# TeslaBMS_Shield_4.net
KiCad netlist of a schematic drawn in EAGLE
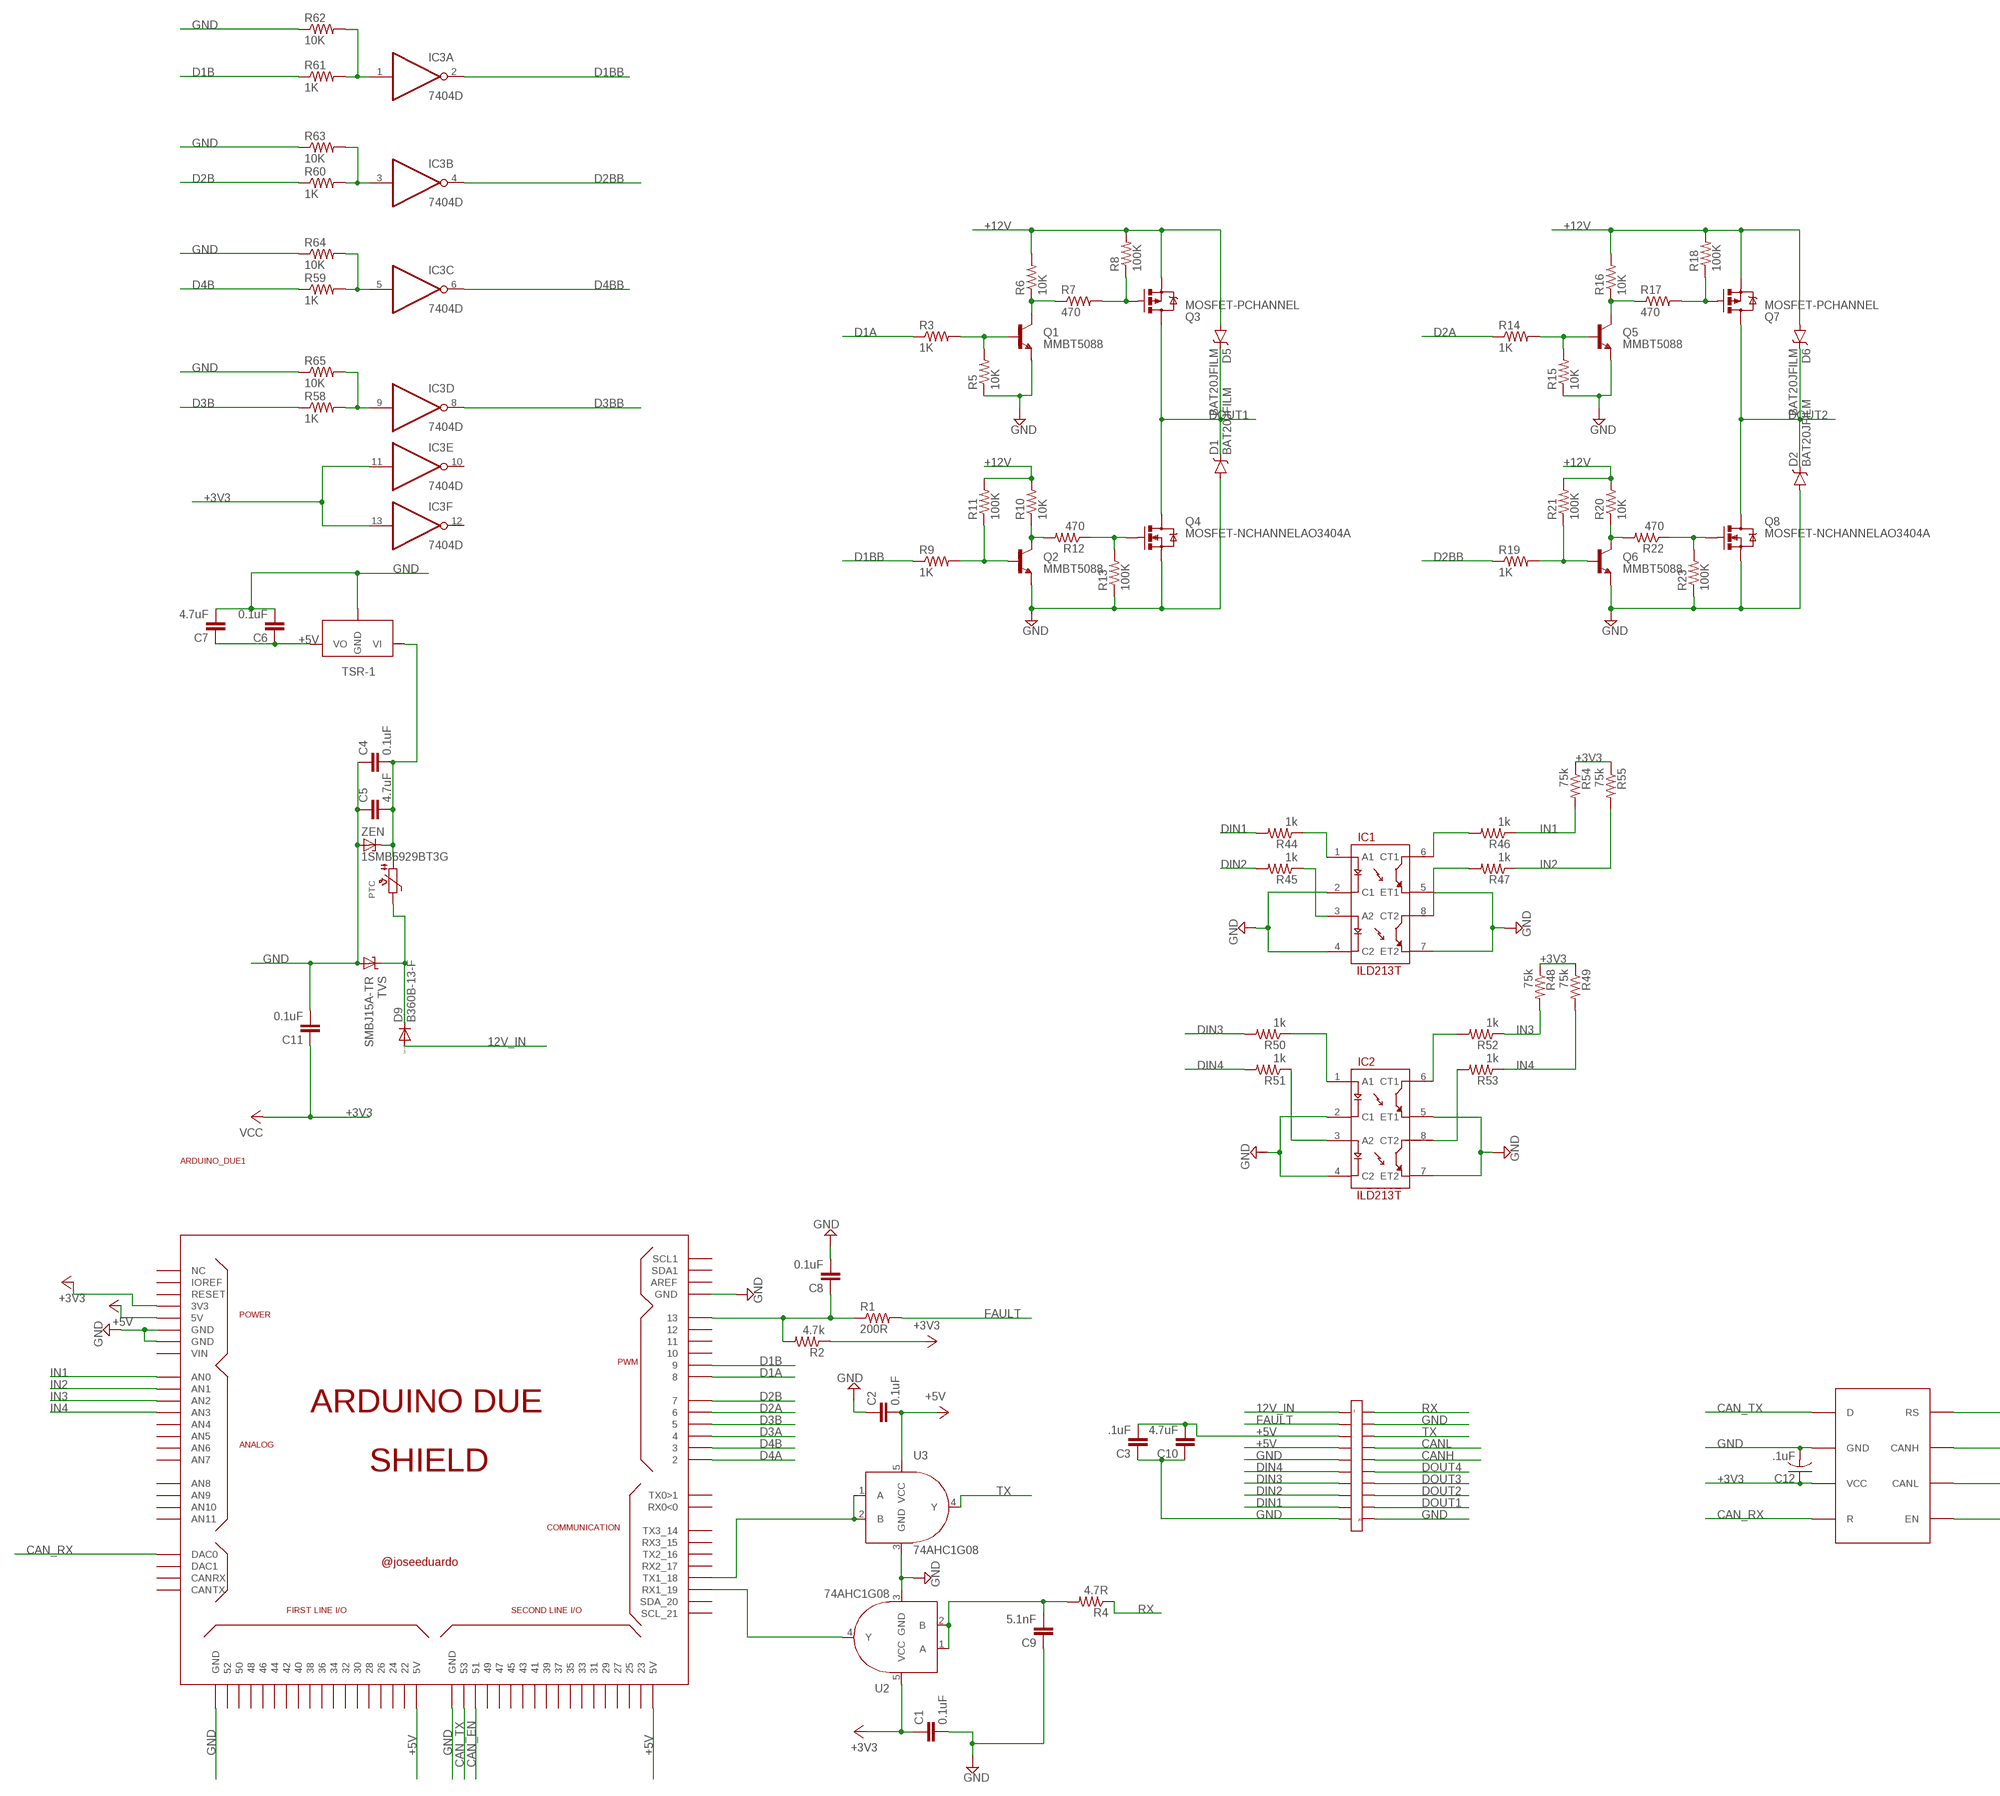
[diagram p0: schematic, sheet 1, part 1 of 2]
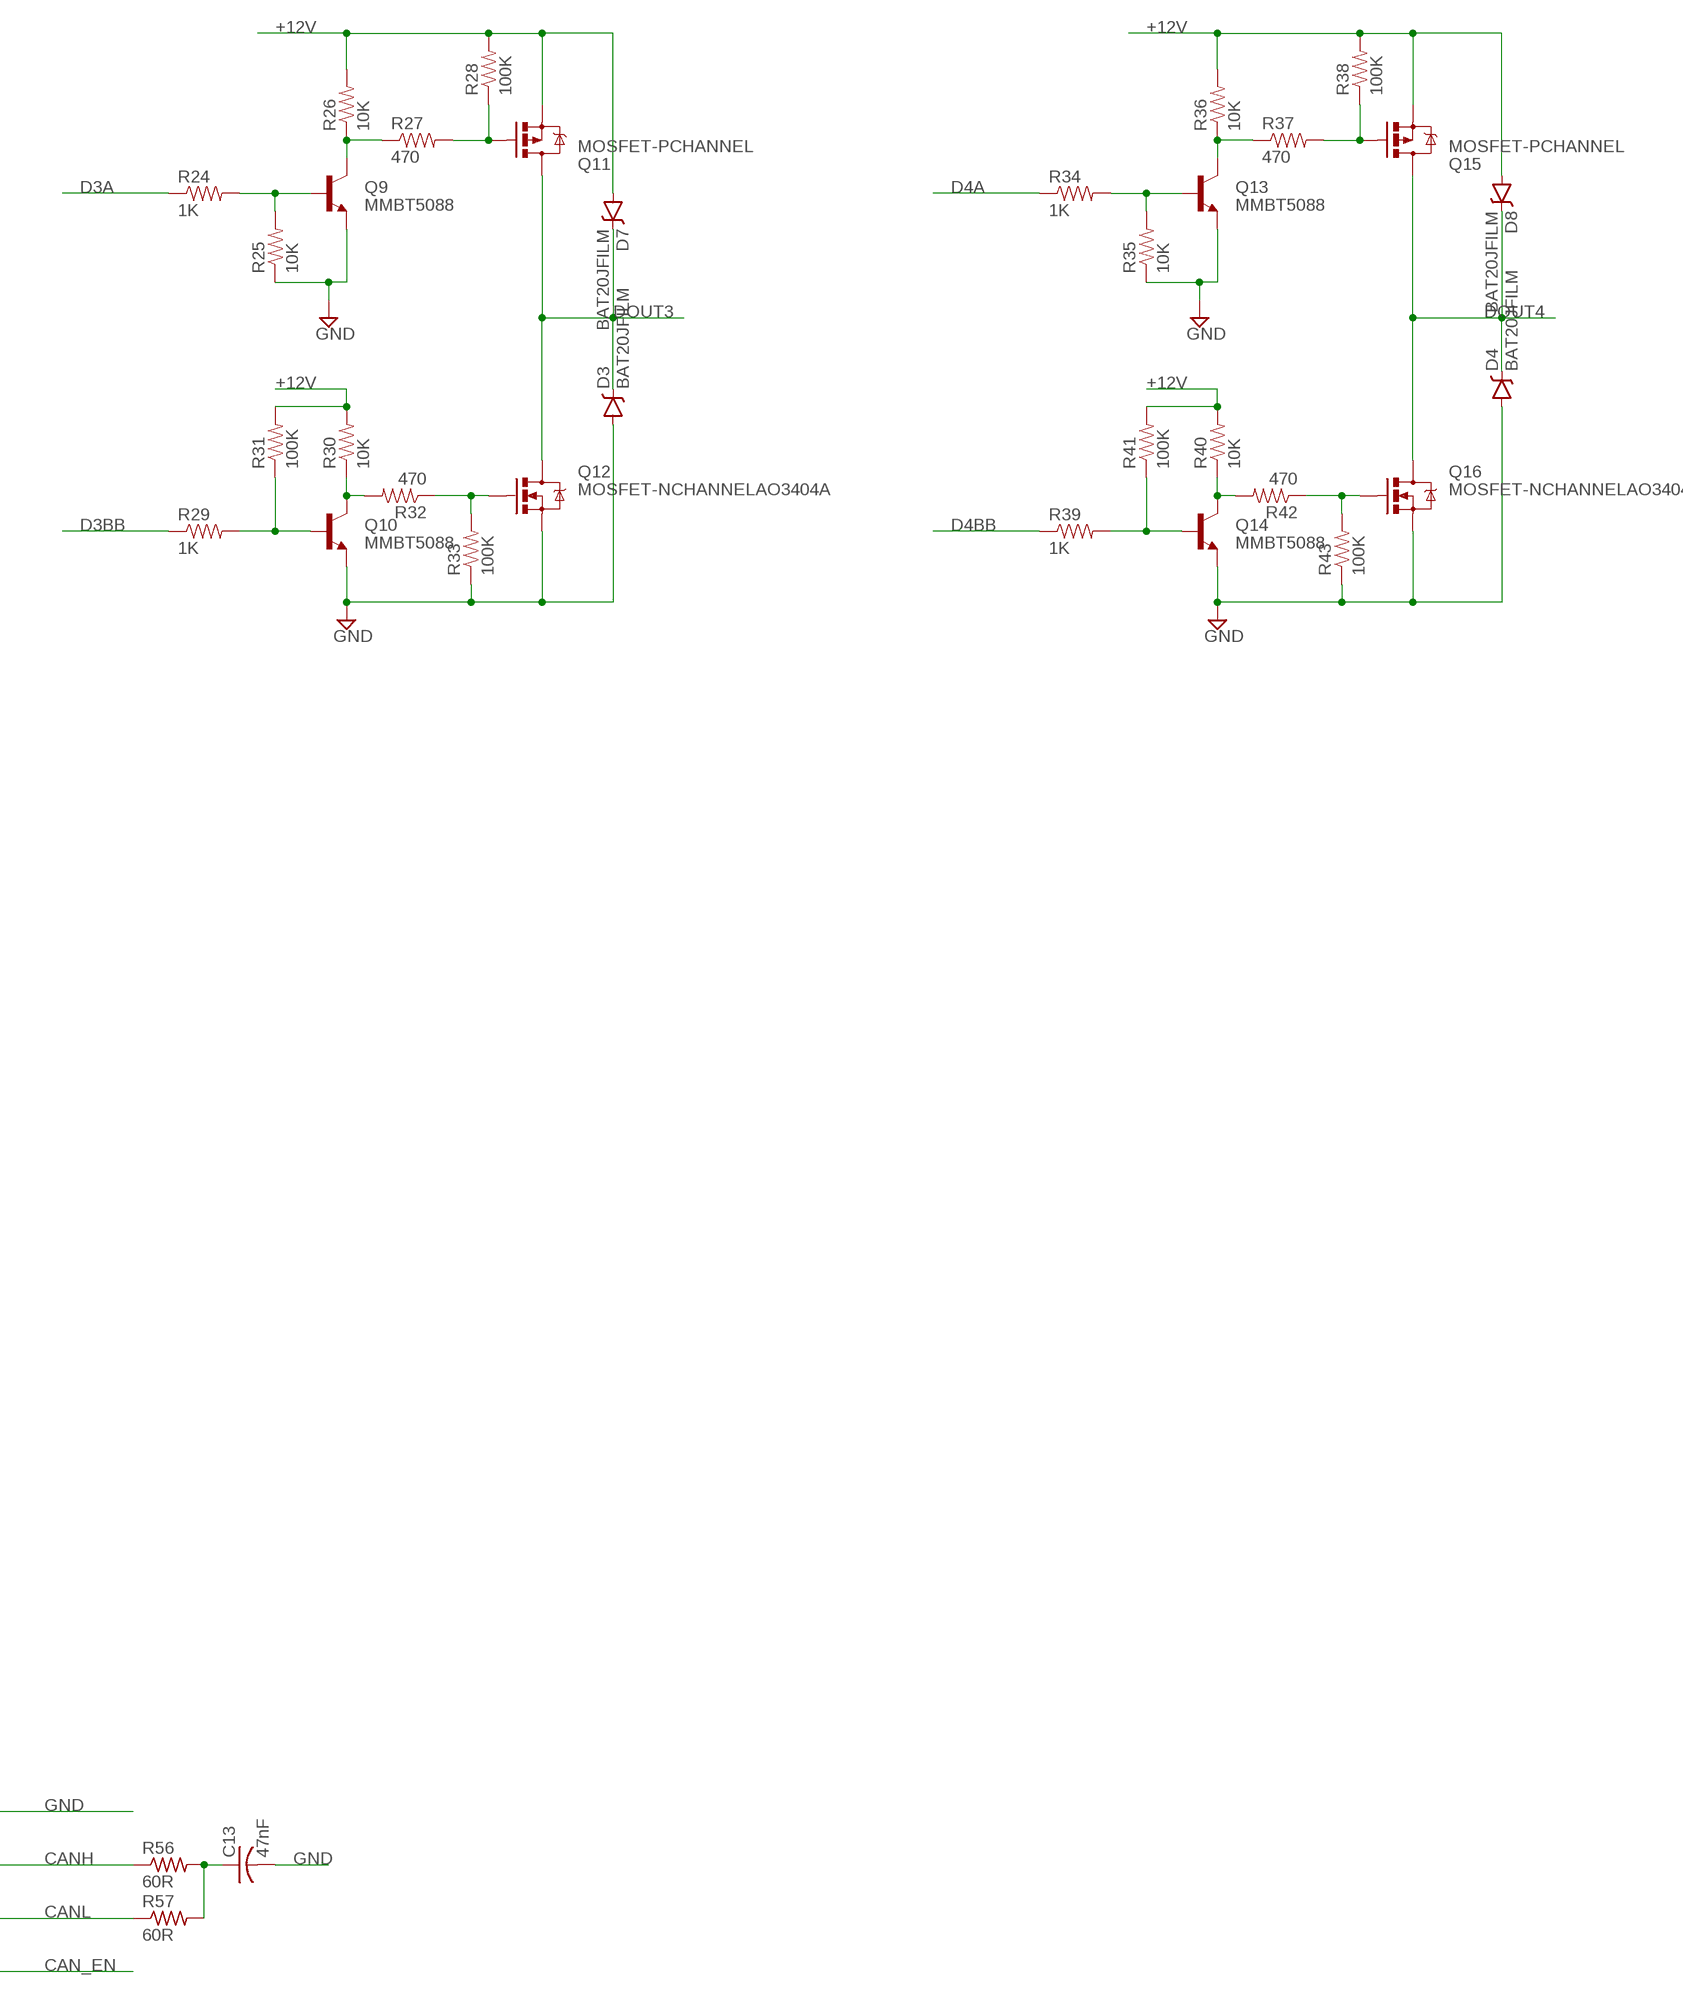
[diagram p1: schematic, sheet 1, part 2 of 2]

(export (version "E")
  (design (tool "Eeschema 10.0.6"))
  (components
    (comp (ref "ARDUINO_DUE1")
      (value "ARDUINO_DUE_SHIELD")
      (footprint "eagle-import:ARDUINO_DUE_SHIELD")
      (libsource (lib "eagle-import") (part "ARDUINO_DUE_SHIELD"))
    )
    (comp (ref "C1")
      (value "0.1uF")
      (footprint "eagle-import:0603-CAP")
      (libsource (lib "eagle-import") (part "CAP0603-CAP"))
    )
    (comp (ref "C2")
      (value "0.1uF")
      (footprint "eagle-import:0603-CAP")
      (libsource (lib "eagle-import") (part "CAP0603-CAP"))
    )
    (comp (ref "C3")
      (value ".1uF")
      (footprint "eagle-import:0603-CAP")
      (libsource (lib "eagle-import") (part "CAP0603-CAP"))
    )
    (comp (ref "C4")
      (value "0.1uF")
      (footprint "eagle-import:0805")
      (libsource (lib "eagle-import") (part "CAP0805"))
    )
    (comp (ref "C5")
      (value "4.7uF")
      (footprint "eagle-import:0805")
      (libsource (lib "eagle-import") (part "CAP0805"))
    )
    (comp (ref "C6")
      (value "0.1uF")
      (footprint "eagle-import:0805")
      (libsource (lib "eagle-import") (part "CAP0805"))
    )
    (comp (ref "C7")
      (value "4.7uF")
      (footprint "eagle-import:0805")
      (libsource (lib "eagle-import") (part "CAP0805"))
    )
    (comp (ref "C8")
      (value "0.1uF")
      (footprint "eagle-import:0603-CAP")
      (libsource (lib "eagle-import") (part "CAP0603-CAP"))
    )
    (comp (ref "C9")
      (value "5.1nF")
      (footprint "eagle-import:0603-CAP")
      (libsource (lib "eagle-import") (part "CAP0603-CAP"))
    )
    (comp (ref "C10")
      (value "4.7uF")
      (footprint "eagle-import:0603-CAP")
      (libsource (lib "eagle-import") (part "CAP0603-CAP"))
    )
    (comp (ref "C11")
      (value "0.1uF")
      (footprint "eagle-import:0805")
      (libsource (lib "eagle-import") (part "CAP0805"))
    )
    (comp (ref "C12")
      (value ".1uF")
      (footprint "eagle-import:C0603")
      (libsource (lib "eagle-import") (part "C-USC0603"))
    )
    (comp (ref "C13")
      (value "47nF")
      (footprint "eagle-import:C0805")
      (libsource (lib "eagle-import") (part "C-USC0805"))
    )
    (comp (ref "D1")
      (value "BAT20JFILM")
      (footprint "eagle-import:SOD-323")
      (libsource (lib "eagle-import") (part "BAT20JFILM"))
    )
    (comp (ref "D2")
      (value "BAT20JFILM")
      (footprint "eagle-import:SOD-323")
      (libsource (lib "eagle-import") (part "BAT20JFILM"))
    )
    (comp (ref "D3")
      (value "BAT20JFILM")
      (footprint "eagle-import:SOD-323")
      (libsource (lib "eagle-import") (part "BAT20JFILM"))
    )
    (comp (ref "D4")
      (value "BAT20JFILM")
      (footprint "eagle-import:SOD-323")
      (libsource (lib "eagle-import") (part "BAT20JFILM"))
    )
    (comp (ref "D5")
      (value "BAT20JFILM")
      (footprint "eagle-import:SOD-323")
      (libsource (lib "eagle-import") (part "BAT20JFILM"))
    )
    (comp (ref "D6")
      (value "BAT20JFILM")
      (footprint "eagle-import:SOD-323")
      (libsource (lib "eagle-import") (part "BAT20JFILM"))
    )
    (comp (ref "D7")
      (value "BAT20JFILM")
      (footprint "eagle-import:SOD-323")
      (libsource (lib "eagle-import") (part "BAT20JFILM"))
    )
    (comp (ref "D8")
      (value "BAT20JFILM")
      (footprint "eagle-import:SOD-323")
      (libsource (lib "eagle-import") (part "BAT20JFILM"))
    )
    (comp (ref "D9")
      (value "B360B-13-F")
      (footprint "eagle-import:SMB")
      (libsource (lib "eagle-import") (part "DIODE-SMB"))
    )
    (comp (ref "IC1")
      (value "ILD213T")
      (footprint "eagle-import:SO08")
      (libsource (lib "eagle-import") (part "ILD213T"))
    )
    (comp (ref "IC2")
      (value "ILD213T")
      (footprint "eagle-import:SO08")
      (libsource (lib "eagle-import") (part "ILD213T"))
    )
    (comp (ref "IC3")
      (value "7404D")
      (footprint "eagle-import:SO14")
      (libsource (lib "eagle-import") (part "7404D"))
    )
    (comp (ref "PTC")
      (value "PTC1812")
      (footprint "eagle-import:PTC1812")
      (libsource (lib "eagle-import") (part "PTC1812"))
    )
    (comp (ref "Q1")
      (value "MMBT5088")
      (footprint "eagle-import:SOT23-3")
      (libsource (lib "eagle-import") (part "TRANSISTOR_NPNMMBT5088"))
    )
    (comp (ref "Q2")
      (value "MMBT5088")
      (footprint "eagle-import:SOT23-3")
      (libsource (lib "eagle-import") (part "TRANSISTOR_NPNMMBT5088"))
    )
    (comp (ref "Q3")
      (value "MOSFET-PCHANNEL")
      (footprint "eagle-import:SOT23-3")
      (libsource (lib "eagle-import") (part "MOSFET-PCHANNEL"))
    )
    (comp (ref "Q4")
      (value "MOSFET-NCHANNELAO3404A")
      (footprint "eagle-import:SOT23-3")
      (libsource (lib "eagle-import") (part "MOSFET-NCHANNELAO3404A"))
    )
    (comp (ref "Q5")
      (value "MMBT5088")
      (footprint "eagle-import:SOT23-3")
      (libsource (lib "eagle-import") (part "TRANSISTOR_NPNMMBT5088"))
    )
    (comp (ref "Q6")
      (value "MMBT5088")
      (footprint "eagle-import:SOT23-3")
      (libsource (lib "eagle-import") (part "TRANSISTOR_NPNMMBT5088"))
    )
    (comp (ref "Q7")
      (value "MOSFET-PCHANNEL")
      (footprint "eagle-import:SOT23-3")
      (libsource (lib "eagle-import") (part "MOSFET-PCHANNEL"))
    )
    (comp (ref "Q8")
      (value "MOSFET-NCHANNELAO3404A")
      (footprint "eagle-import:SOT23-3")
      (libsource (lib "eagle-import") (part "MOSFET-NCHANNELAO3404A"))
    )
    (comp (ref "Q9")
      (value "MMBT5088")
      (footprint "eagle-import:SOT23-3")
      (libsource (lib "eagle-import") (part "TRANSISTOR_NPNMMBT5088"))
    )
    (comp (ref "Q10")
      (value "MMBT5088")
      (footprint "eagle-import:SOT23-3")
      (libsource (lib "eagle-import") (part "TRANSISTOR_NPNMMBT5088"))
    )
    (comp (ref "Q11")
      (value "MOSFET-PCHANNEL")
      (footprint "eagle-import:SOT23-3")
      (libsource (lib "eagle-import") (part "MOSFET-PCHANNEL"))
    )
    (comp (ref "Q12")
      (value "MOSFET-NCHANNELAO3404A")
      (footprint "eagle-import:SOT23-3")
      (libsource (lib "eagle-import") (part "MOSFET-NCHANNELAO3404A"))
    )
    (comp (ref "Q13")
      (value "MMBT5088")
      (footprint "eagle-import:SOT23-3")
      (libsource (lib "eagle-import") (part "TRANSISTOR_NPNMMBT5088"))
    )
    (comp (ref "Q14")
      (value "MMBT5088")
      (footprint "eagle-import:SOT23-3")
      (libsource (lib "eagle-import") (part "TRANSISTOR_NPNMMBT5088"))
    )
    (comp (ref "Q15")
      (value "MOSFET-PCHANNEL")
      (footprint "eagle-import:SOT23-3")
      (libsource (lib "eagle-import") (part "MOSFET-PCHANNEL"))
    )
    (comp (ref "Q16")
      (value "MOSFET-NCHANNELAO3404A")
      (footprint "eagle-import:SOT23-3")
      (libsource (lib "eagle-import") (part "MOSFET-NCHANNELAO3404A"))
    )
    (comp (ref "R1")
      (value "200R")
      (footprint "eagle-import:0603-RES")
      (libsource (lib "eagle-import") (part "RESISTOR0603-RES"))
    )
    (comp (ref "R2")
      (value "4.7k")
      (footprint "eagle-import:0603-RES")
      (libsource (lib "eagle-import") (part "RESISTOR0603-RES"))
    )
    (comp (ref "R3")
      (value "1K")
      (footprint "eagle-import:0402-RES")
      (libsource (lib "eagle-import") (part "RESISTOR0402"))
    )
    (comp (ref "R4")
      (value "4.7R")
      (footprint "eagle-import:0603-RES")
      (libsource (lib "eagle-import") (part "RESISTOR0603-RES"))
    )
    (comp (ref "R5")
      (value "10K")
      (footprint "eagle-import:0402-RES")
      (libsource (lib "eagle-import") (part "RESISTOR0402"))
    )
    (comp (ref "R6")
      (value "10K")
      (footprint "eagle-import:0402-RES")
      (libsource (lib "eagle-import") (part "RESISTOR0402"))
    )
    (comp (ref "R7")
      (value "470")
      (footprint "eagle-import:0402-RES")
      (libsource (lib "eagle-import") (part "RESISTOR0402"))
    )
    (comp (ref "R8")
      (value "100K")
      (footprint "eagle-import:0402-RES")
      (libsource (lib "eagle-import") (part "RESISTOR0402"))
    )
    (comp (ref "R9")
      (value "1K")
      (footprint "eagle-import:0402-RES")
      (libsource (lib "eagle-import") (part "RESISTOR0402"))
    )
    (comp (ref "R10")
      (value "10K")
      (footprint "eagle-import:0402-RES")
      (libsource (lib "eagle-import") (part "RESISTOR0402"))
    )
    (comp (ref "R11")
      (value "100K")
      (footprint "eagle-import:0402-RES")
      (libsource (lib "eagle-import") (part "RESISTOR0402"))
    )
    (comp (ref "R12")
      (value "470")
      (footprint "eagle-import:0402-RES")
      (libsource (lib "eagle-import") (part "RESISTOR0402"))
    )
    (comp (ref "R13")
      (value "100K")
      (footprint "eagle-import:0402-RES")
      (libsource (lib "eagle-import") (part "RESISTOR0402"))
    )
    (comp (ref "R14")
      (value "1K")
      (footprint "eagle-import:0402-RES")
      (libsource (lib "eagle-import") (part "RESISTOR0402"))
    )
    (comp (ref "R15")
      (value "10K")
      (footprint "eagle-import:0402-RES")
      (libsource (lib "eagle-import") (part "RESISTOR0402"))
    )
    (comp (ref "R16")
      (value "10K")
      (footprint "eagle-import:0402-RES")
      (libsource (lib "eagle-import") (part "RESISTOR0402"))
    )
    (comp (ref "R17")
      (value "470")
      (footprint "eagle-import:0402-RES")
      (libsource (lib "eagle-import") (part "RESISTOR0402"))
    )
    (comp (ref "R18")
      (value "100K")
      (footprint "eagle-import:0402-RES")
      (libsource (lib "eagle-import") (part "RESISTOR0402"))
    )
    (comp (ref "R19")
      (value "1K")
      (footprint "eagle-import:0402-RES")
      (libsource (lib "eagle-import") (part "RESISTOR0402"))
    )
    (comp (ref "R20")
      (value "10K")
      (footprint "eagle-import:0402-RES")
      (libsource (lib "eagle-import") (part "RESISTOR0402"))
    )
    (comp (ref "R21")
      (value "100K")
      (footprint "eagle-import:0402-RES")
      (libsource (lib "eagle-import") (part "RESISTOR0402"))
    )
    (comp (ref "R22")
      (value "470")
      (footprint "eagle-import:0402-RES")
      (libsource (lib "eagle-import") (part "RESISTOR0402"))
    )
    (comp (ref "R23")
      (value "100K")
      (footprint "eagle-import:0402-RES")
      (libsource (lib "eagle-import") (part "RESISTOR0402"))
    )
    (comp (ref "R24")
      (value "1K")
      (footprint "eagle-import:0402-RES")
      (libsource (lib "eagle-import") (part "RESISTOR0402"))
    )
    (comp (ref "R25")
      (value "10K")
      (footprint "eagle-import:0402-RES")
      (libsource (lib "eagle-import") (part "RESISTOR0402"))
    )
    (comp (ref "R26")
      (value "10K")
      (footprint "eagle-import:0402-RES")
      (libsource (lib "eagle-import") (part "RESISTOR0402"))
    )
    (comp (ref "R27")
      (value "470")
      (footprint "eagle-import:0402-RES")
      (libsource (lib "eagle-import") (part "RESISTOR0402"))
    )
    (comp (ref "R28")
      (value "100K")
      (footprint "eagle-import:0402-RES")
      (libsource (lib "eagle-import") (part "RESISTOR0402"))
    )
    (comp (ref "R29")
      (value "1K")
      (footprint "eagle-import:0402-RES")
      (libsource (lib "eagle-import") (part "RESISTOR0402"))
    )
    (comp (ref "R30")
      (value "10K")
      (footprint "eagle-import:0402-RES")
      (libsource (lib "eagle-import") (part "RESISTOR0402"))
    )
    (comp (ref "R31")
      (value "100K")
      (footprint "eagle-import:0402-RES")
      (libsource (lib "eagle-import") (part "RESISTOR0402"))
    )
    (comp (ref "R32")
      (value "470")
      (footprint "eagle-import:0402-RES")
      (libsource (lib "eagle-import") (part "RESISTOR0402"))
    )
    (comp (ref "R33")
      (value "100K")
      (footprint "eagle-import:0402-RES")
      (libsource (lib "eagle-import") (part "RESISTOR0402"))
    )
    (comp (ref "R34")
      (value "1K")
      (footprint "eagle-import:0402-RES")
      (libsource (lib "eagle-import") (part "RESISTOR0402"))
    )
    (comp (ref "R35")
      (value "10K")
      (footprint "eagle-import:0402-RES")
      (libsource (lib "eagle-import") (part "RESISTOR0402"))
    )
    (comp (ref "R36")
      (value "10K")
      (footprint "eagle-import:0402-RES")
      (libsource (lib "eagle-import") (part "RESISTOR0402"))
    )
    (comp (ref "R37")
      (value "470")
      (footprint "eagle-import:0402-RES")
      (libsource (lib "eagle-import") (part "RESISTOR0402"))
    )
    (comp (ref "R38")
      (value "100K")
      (footprint "eagle-import:0402-RES")
      (libsource (lib "eagle-import") (part "RESISTOR0402"))
    )
    (comp (ref "R39")
      (value "1K")
      (footprint "eagle-import:0402-RES")
      (libsource (lib "eagle-import") (part "RESISTOR0402"))
    )
    (comp (ref "R40")
      (value "10K")
      (footprint "eagle-import:0402-RES")
      (libsource (lib "eagle-import") (part "RESISTOR0402"))
    )
    (comp (ref "R41")
      (value "100K")
      (footprint "eagle-import:0402-RES")
      (libsource (lib "eagle-import") (part "RESISTOR0402"))
    )
    (comp (ref "R42")
      (value "470")
      (footprint "eagle-import:0402-RES")
      (libsource (lib "eagle-import") (part "RESISTOR0402"))
    )
    (comp (ref "R43")
      (value "100K")
      (footprint "eagle-import:0402-RES")
      (libsource (lib "eagle-import") (part "RESISTOR0402"))
    )
    (comp (ref "R44")
      (value "1k")
      (footprint "eagle-import:0603-RES")
      (libsource (lib "eagle-import") (part "RESISTOR0603-RES"))
    )
    (comp (ref "R45")
      (value "1k")
      (footprint "eagle-import:0603-RES")
      (libsource (lib "eagle-import") (part "RESISTOR0603-RES"))
    )
    (comp (ref "R46")
      (value "1k")
      (footprint "eagle-import:0603-RES")
      (libsource (lib "eagle-import") (part "RESISTOR0603-RES"))
    )
    (comp (ref "R47")
      (value "1k")
      (footprint "eagle-import:0603-RES")
      (libsource (lib "eagle-import") (part "RESISTOR0603-RES"))
    )
    (comp (ref "R48")
      (value "75k")
      (footprint "eagle-import:0603-RES")
      (libsource (lib "eagle-import") (part "RESISTOR0603-RES"))
    )
    (comp (ref "R49")
      (value "75k")
      (footprint "eagle-import:0603-RES")
      (libsource (lib "eagle-import") (part "RESISTOR0603-RES"))
    )
    (comp (ref "R50")
      (value "1k")
      (footprint "eagle-import:0603-RES")
      (libsource (lib "eagle-import") (part "RESISTOR0603-RES"))
    )
    (comp (ref "R51")
      (value "1k")
      (footprint "eagle-import:0603-RES")
      (libsource (lib "eagle-import") (part "RESISTOR0603-RES"))
    )
    (comp (ref "R52")
      (value "1k")
      (footprint "eagle-import:0603-RES")
      (libsource (lib "eagle-import") (part "RESISTOR0603-RES"))
    )
    (comp (ref "R53")
      (value "1k")
      (footprint "eagle-import:0603-RES")
      (libsource (lib "eagle-import") (part "RESISTOR0603-RES"))
    )
    (comp (ref "R54")
      (value "75k")
      (footprint "eagle-import:0603-RES")
      (libsource (lib "eagle-import") (part "RESISTOR0603-RES"))
    )
    (comp (ref "R55")
      (value "75k")
      (footprint "eagle-import:0603-RES")
      (libsource (lib "eagle-import") (part "RESISTOR0603-RES"))
    )
    (comp (ref "R56")
      (value "60R")
      (footprint "eagle-import:M0805")
      (libsource (lib "eagle-import") (part "R-US_M0805"))
    )
    (comp (ref "R57")
      (value "60R")
      (footprint "eagle-import:M0805")
      (libsource (lib "eagle-import") (part "R-US_M0805"))
    )
    (comp (ref "R58")
      (value "1K")
      (footprint "eagle-import:0402-RES")
      (libsource (lib "eagle-import") (part "RESISTOR0402"))
    )
    (comp (ref "R59")
      (value "1K")
      (footprint "eagle-import:0402-RES")
      (libsource (lib "eagle-import") (part "RESISTOR0402"))
    )
    (comp (ref "R60")
      (value "1K")
      (footprint "eagle-import:0402-RES")
      (libsource (lib "eagle-import") (part "RESISTOR0402"))
    )
    (comp (ref "R61")
      (value "1K")
      (footprint "eagle-import:0402-RES")
      (libsource (lib "eagle-import") (part "RESISTOR0402"))
    )
    (comp (ref "R62")
      (value "10K")
      (footprint "eagle-import:0402-RES")
      (libsource (lib "eagle-import") (part "RESISTOR0402"))
    )
    (comp (ref "R63")
      (value "10K")
      (footprint "eagle-import:0402-RES")
      (libsource (lib "eagle-import") (part "RESISTOR0402"))
    )
    (comp (ref "R64")
      (value "10K")
      (footprint "eagle-import:0402-RES")
      (libsource (lib "eagle-import") (part "RESISTOR0402"))
    )
    (comp (ref "R65")
      (value "10K")
      (footprint "eagle-import:0402-RES")
      (libsource (lib "eagle-import") (part "RESISTOR0402"))
    )
    (comp (ref "TVS")
      (value "SMBJ15A-TR")
      (footprint "eagle-import:SMBJ")
      (libsource (lib "eagle-import") (part "SUPPRESSOR-SMBJ"))
    )
    (comp (ref "U$2")
      (value "VAL-U-LOK-20PIN")
      (footprint "eagle-import:VALULOK-20")
      (libsource (lib "eagle-import") (part "VAL-U-LOK-20PIN"))
    )
    (comp (ref "U1")
      (value "SN65HVD234")
      (footprint "eagle-import:SOIC8")
      (libsource (lib "eagle-import") (part "SN65HVD234"))
    )
    (comp (ref "U2")
      (value "74AHC1G08")
      (footprint "eagle-import:SOT353")
      (libsource (lib "eagle-import") (part "74AHC1G08"))
    )
    (comp (ref "U3")
      (value "74AHC1G08")
      (footprint "eagle-import:SOT353")
      (libsource (lib "eagle-import") (part "74AHC1G08"))
    )
    (comp (ref "U9")
      (value "TSR-1")
      (footprint "eagle-import:TSR-1")
      (libsource (lib "eagle-import") (part "TSR-1"))
    )
    (comp (ref "ZEN")
      (value "1SMB5929BT3G")
      (footprint "eagle-import:SMB")
      (libsource (lib "eagle-import") (part "ZENER-DIODESMB"))
    )
  )
  (nets
    (net (code "1") (name "+3V3") (class "Default")
      (node (ref "ARDUINO_DUE1") (pin "3V3") (pinfunction "3V3_3V3") (pintype "bidirectional"))
      (node (ref "C1") (pin "1") (pinfunction "1_1") (pintype "passive"))
      (node (ref "C11") (pin "1") (pinfunction "1_1") (pintype "passive"))
      (node (ref "C12") (pin "1") (pinfunction "1_1") (pintype "passive"))
      (node (ref "IC3") (pin "11") (pinfunction "I_11") (pintype "input"))
      (node (ref "IC3") (pin "13") (pinfunction "I_13") (pintype "input"))
      (node (ref "R2") (pin "1") (pinfunction "1_1") (pintype "passive"))
      (node (ref "R48") (pin "1") (pinfunction "1_1") (pintype "passive"))
      (node (ref "R49") (pin "1") (pinfunction "1_1") (pintype "passive"))
      (node (ref "R54") (pin "1") (pinfunction "1_1") (pintype "passive"))
      (node (ref "R55") (pin "1") (pinfunction "1_1") (pintype "passive"))
      (node (ref "U1") (pin "PIN3") (pinfunction "VCC_PIN3") (pintype "bidirectional"))
      (node (ref "U2") (pin "5") (pinfunction "VCC_5") (pintype "bidirectional"))
    )
    (net (code "2") (name "+5V") (class "Default")
      (node (ref "ARDUINO_DUE1") (pin "5V0") (pinfunction "5V_5V0") (pintype "bidirectional"))
      (node (ref "ARDUINO_DUE1") (pin "5V0_1") (pinfunction "5V_5V0_1") (pintype "bidirectional"))
      (node (ref "ARDUINO_DUE1") (pin "5V0_2") (pinfunction "5V_5V0_2") (pintype "bidirectional"))
      (node (ref "C10") (pin "2") (pinfunction "2_2") (pintype "passive"))
      (node (ref "C2") (pin "2") (pinfunction "2_2") (pintype "passive"))
      (node (ref "C3") (pin "2") (pinfunction "2_2") (pintype "passive"))
      (node (ref "C6") (pin "1") (pinfunction "1_1") (pintype "passive"))
      (node (ref "C7") (pin "1") (pinfunction "1_1") (pintype "passive"))
      (node (ref "U$2") (pin "P$3") (pinfunction "P$3_P$3") (pintype "bidirectional"))
      (node (ref "U$2") (pin "P$4") (pinfunction "P$4_P$4") (pintype "bidirectional"))
      (node (ref "U3") (pin "5") (pinfunction "VCC_5") (pintype "bidirectional"))
      (node (ref "U9") (pin "P$3") (pinfunction "VO_P$3") (pintype "bidirectional"))
    )
    (net (code "3") (name "/+12V") (class "Default")
      (node (ref "C4") (pin "2") (pinfunction "2_2") (pintype "passive"))
      (node (ref "C5") (pin "2") (pinfunction "2_2") (pintype "passive"))
      (node (ref "D5") (pin "A") (pinfunction "A_A") (pintype "passive"))
      (node (ref "D6") (pin "A") (pinfunction "A_A") (pintype "passive"))
      (node (ref "D7") (pin "A") (pinfunction "A_A") (pintype "passive"))
      (node (ref "D8") (pin "A") (pinfunction "A_A") (pintype "passive"))
      (node (ref "PTC") (pin "P$1") (pinfunction "1_P$1") (pintype "passive"))
      (node (ref "Q11") (pin "2") (pinfunction "S_2") (pintype "passive"))
      (node (ref "Q15") (pin "2") (pinfunction "S_2") (pintype "passive"))
      (node (ref "Q3") (pin "2") (pinfunction "S_2") (pintype "passive"))
      (node (ref "Q7") (pin "2") (pinfunction "S_2") (pintype "passive"))
      (node (ref "R10") (pin "2") (pinfunction "2_2") (pintype "passive"))
      (node (ref "R11") (pin "2") (pinfunction "2_2") (pintype "passive"))
      (node (ref "R16") (pin "2") (pinfunction "2_2") (pintype "passive"))
      (node (ref "R18") (pin "2") (pinfunction "2_2") (pintype "passive"))
      (node (ref "R20") (pin "2") (pinfunction "2_2") (pintype "passive"))
      (node (ref "R21") (pin "2") (pinfunction "2_2") (pintype "passive"))
      (node (ref "R26") (pin "2") (pinfunction "2_2") (pintype "passive"))
      (node (ref "R28") (pin "2") (pinfunction "2_2") (pintype "passive"))
      (node (ref "R30") (pin "2") (pinfunction "2_2") (pintype "passive"))
      (node (ref "R31") (pin "2") (pinfunction "2_2") (pintype "passive"))
      (node (ref "R36") (pin "2") (pinfunction "2_2") (pintype "passive"))
      (node (ref "R38") (pin "2") (pinfunction "2_2") (pintype "passive"))
      (node (ref "R40") (pin "2") (pinfunction "2_2") (pintype "passive"))
      (node (ref "R41") (pin "2") (pinfunction "2_2") (pintype "passive"))
      (node (ref "R6") (pin "2") (pinfunction "2_2") (pintype "passive"))
      (node (ref "R8") (pin "2") (pinfunction "2_2") (pintype "passive"))
      (node (ref "U9") (pin "P$1") (pinfunction "VI_P$1") (pintype "bidirectional"))
      (node (ref "ZEN") (pin "C") (pinfunction "C_C") (pintype "passive"))
    )
    (net (code "4") (name "/12V_IN") (class "Default")
      (node (ref "D9") (pin "A") (pinfunction "A_A") (pintype "passive"))
      (node (ref "U$2") (pin "P$1") (pinfunction "P$1_P$1") (pintype "bidirectional"))
    )
    (net (code "5") (name "/CANH") (class "Default")
      (node (ref "R56") (pin "1") (pinfunction "1_1") (pintype "passive"))
      (node (ref "U$2") (pin "P$15") (pinfunction "P$15_P$15") (pintype "bidirectional"))
      (node (ref "U1") (pin "PIN7") (pinfunction "CANH_PIN7") (pintype "bidirectional"))
    )
    (net (code "6") (name "/CANL") (class "Default")
      (node (ref "R57") (pin "1") (pinfunction "1_1") (pintype "passive"))
      (node (ref "U$2") (pin "P$14") (pinfunction "P$14_P$14") (pintype "bidirectional"))
      (node (ref "U1") (pin "PIN6") (pinfunction "CANL_PIN6") (pintype "bidirectional"))
    )
    (net (code "7") (name "/CAN_EN") (class "Default")
      (node (ref "ARDUINO_DUE1") (pin "51") (pinfunction "51_51") (pintype "bidirectional"))
      (node (ref "U1") (pin "PIN5") (pinfunction "EN_PIN5") (pintype "bidirectional"))
    )
    (net (code "8") (name "/CAN_RX") (class "Default")
      (node (ref "ARDUINO_DUE1") (pin "DAC0") (pinfunction "DAC0_DAC0") (pintype "bidirectional"))
      (node (ref "U1") (pin "PIN4") (pinfunction "R_PIN4") (pintype "bidirectional"))
    )
    (net (code "9") (name "/CAN_TX") (class "Default")
      (node (ref "ARDUINO_DUE1") (pin "53") (pinfunction "53_53") (pintype "bidirectional"))
      (node (ref "U1") (pin "PIN1") (pinfunction "D_PIN1") (pintype "bidirectional"))
    )
    (net (code "10") (name "/D1A") (class "Default")
      (node (ref "ARDUINO_DUE1") (pin "8") (pinfunction "8_8") (pintype "bidirectional"))
      (node (ref "R3") (pin "1") (pinfunction "1_1") (pintype "passive"))
    )
    (net (code "11") (name "/D1B") (class "Default")
      (node (ref "ARDUINO_DUE1") (pin "9") (pinfunction "9_9") (pintype "bidirectional"))
      (node (ref "R61") (pin "1") (pinfunction "1_1") (pintype "passive"))
    )
    (net (code "12") (name "/D1BB") (class "Default")
      (node (ref "IC3") (pin "2") (pinfunction "O_2") (pintype "output"))
      (node (ref "R9") (pin "1") (pinfunction "1_1") (pintype "passive"))
    )
    (net (code "13") (name "/D2A") (class "Default")
      (node (ref "ARDUINO_DUE1") (pin "6") (pinfunction "6_6") (pintype "bidirectional"))
      (node (ref "R14") (pin "1") (pinfunction "1_1") (pintype "passive"))
    )
    (net (code "14") (name "/D2B") (class "Default")
      (node (ref "ARDUINO_DUE1") (pin "7") (pinfunction "7_7") (pintype "bidirectional"))
      (node (ref "R60") (pin "1") (pinfunction "1_1") (pintype "passive"))
    )
    (net (code "15") (name "/D2BB") (class "Default")
      (node (ref "IC3") (pin "4") (pinfunction "O_4") (pintype "output"))
      (node (ref "R19") (pin "1") (pinfunction "1_1") (pintype "passive"))
    )
    (net (code "16") (name "/D3A") (class "Default")
      (node (ref "ARDUINO_DUE1") (pin "4") (pinfunction "4_4") (pintype "bidirectional"))
      (node (ref "R24") (pin "1") (pinfunction "1_1") (pintype "passive"))
    )
    (net (code "17") (name "/D3B") (class "Default")
      (node (ref "ARDUINO_DUE1") (pin "5") (pinfunction "5_5") (pintype "bidirectional"))
      (node (ref "R58") (pin "1") (pinfunction "1_1") (pintype "passive"))
    )
    (net (code "18") (name "/D3BB") (class "Default")
      (node (ref "IC3") (pin "8") (pinfunction "O_8") (pintype "output"))
      (node (ref "R29") (pin "1") (pinfunction "1_1") (pintype "passive"))
    )
    (net (code "19") (name "/D4A") (class "Default")
      (node (ref "ARDUINO_DUE1") (pin "2") (pinfunction "2_2") (pintype "bidirectional"))
      (node (ref "R34") (pin "1") (pinfunction "1_1") (pintype "passive"))
    )
    (net (code "20") (name "/D4B") (class "Default")
      (node (ref "ARDUINO_DUE1") (pin "3") (pinfunction "3_3") (pintype "bidirectional"))
      (node (ref "R59") (pin "1") (pinfunction "1_1") (pintype "passive"))
    )
    (net (code "21") (name "/D4BB") (class "Default")
      (node (ref "IC3") (pin "6") (pinfunction "O_6") (pintype "output"))
      (node (ref "R39") (pin "1") (pinfunction "1_1") (pintype "passive"))
    )
    (net (code "22") (name "/DIN1") (class "Default")
      (node (ref "R44") (pin "2") (pinfunction "2_2") (pintype "passive"))
      (node (ref "U$2") (pin "P$9") (pinfunction "P$9_P$9") (pintype "bidirectional"))
    )
    (net (code "23") (name "/DIN2") (class "Default")
      (node (ref "R45") (pin "2") (pinfunction "2_2") (pintype "passive"))
      (node (ref "U$2") (pin "P$8") (pinfunction "P$8_P$8") (pintype "bidirectional"))
    )
    (net (code "24") (name "/DIN3") (class "Default")
      (node (ref "R50") (pin "2") (pinfunction "2_2") (pintype "passive"))
      (node (ref "U$2") (pin "P$7") (pinfunction "P$7_P$7") (pintype "bidirectional"))
    )
    (net (code "25") (name "/DIN4") (class "Default")
      (node (ref "R51") (pin "2") (pinfunction "2_2") (pintype "passive"))
      (node (ref "U$2") (pin "P$6") (pinfunction "P$6_P$6") (pintype "bidirectional"))
    )
    (net (code "26") (name "/DOUT1") (class "Default")
      (node (ref "D1") (pin "C") (pinfunction "C_C") (pintype "passive"))
      (node (ref "D5") (pin "C") (pinfunction "C_C") (pintype "passive"))
      (node (ref "Q3") (pin "3") (pinfunction "D_3") (pintype "passive"))
      (node (ref "Q4") (pin "3") (pinfunction "D_3") (pintype "passive"))
      (node (ref "U$2") (pin "P$19") (pinfunction "P$19_P$19") (pintype "bidirectional"))
    )
    (net (code "27") (name "/DOUT2") (class "Default")
      (node (ref "D2") (pin "C") (pinfunction "C_C") (pintype "passive"))
      (node (ref "D6") (pin "C") (pinfunction "C_C") (pintype "passive"))
      (node (ref "Q7") (pin "3") (pinfunction "D_3") (pintype "passive"))
      (node (ref "Q8") (pin "3") (pinfunction "D_3") (pintype "passive"))
      (node (ref "U$2") (pin "P$18") (pinfunction "P$18_P$18") (pintype "bidirectional"))
    )
    (net (code "28") (name "/DOUT3") (class "Default")
      (node (ref "D3") (pin "C") (pinfunction "C_C") (pintype "passive"))
      (node (ref "D7") (pin "C") (pinfunction "C_C") (pintype "passive"))
      (node (ref "Q11") (pin "3") (pinfunction "D_3") (pintype "passive"))
      (node (ref "Q12") (pin "3") (pinfunction "D_3") (pintype "passive"))
      (node (ref "U$2") (pin "P$17") (pinfunction "P$17_P$17") (pintype "bidirectional"))
    )
    (net (code "29") (name "/DOUT4") (class "Default")
      (node (ref "D4") (pin "C") (pinfunction "C_C") (pintype "passive"))
      (node (ref "D8") (pin "C") (pinfunction "C_C") (pintype "passive"))
      (node (ref "Q15") (pin "3") (pinfunction "D_3") (pintype "passive"))
      (node (ref "Q16") (pin "3") (pinfunction "D_3") (pintype "passive"))
      (node (ref "U$2") (pin "P$16") (pinfunction "P$16_P$16") (pintype "bidirectional"))
    )
    (net (code "30") (name "/FAULT") (class "Default")
      (node (ref "R1") (pin "2") (pinfunction "2_2") (pintype "passive"))
      (node (ref "U$2") (pin "P$2") (pinfunction "P$2_P$2") (pintype "bidirectional"))
    )
    (net (code "31") (name "/IN1") (class "Default")
      (node (ref "ARDUINO_DUE1") (pin "A0") (pinfunction "AN0_A0") (pintype "bidirectional"))
      (node (ref "R46") (pin "1") (pinfunction "1_1") (pintype "passive"))
      (node (ref "R54") (pin "2") (pinfunction "2_2") (pintype "passive"))
    )
    (net (code "32") (name "/IN2") (class "Default")
      (node (ref "ARDUINO_DUE1") (pin "A1") (pinfunction "AN1_A1") (pintype "bidirectional"))
      (node (ref "R47") (pin "1") (pinfunction "1_1") (pintype "passive"))
      (node (ref "R55") (pin "2") (pinfunction "2_2") (pintype "passive"))
    )
    (net (code "33") (name "/IN3") (class "Default")
      (node (ref "ARDUINO_DUE1") (pin "A2") (pinfunction "AN2_A2") (pintype "bidirectional"))
      (node (ref "R48") (pin "2") (pinfunction "2_2") (pintype "passive"))
      (node (ref "R52") (pin "1") (pinfunction "1_1") (pintype "passive"))
    )
    (net (code "34") (name "/IN4") (class "Default")
      (node (ref "ARDUINO_DUE1") (pin "A3") (pinfunction "AN3_A3") (pintype "bidirectional"))
      (node (ref "R49") (pin "2") (pinfunction "2_2") (pintype "passive"))
      (node (ref "R53") (pin "1") (pinfunction "1_1") (pintype "passive"))
    )
    (net (code "35") (name "/RX") (class "Default")
      (node (ref "R4") (pin "1") (pinfunction "1_1") (pintype "passive"))
      (node (ref "U$2") (pin "P$11") (pinfunction "P$11_P$11") (pintype "bidirectional"))
    )
    (net (code "36") (name "/TX") (class "Default")
      (node (ref "U$2") (pin "P$13") (pinfunction "P$13_P$13") (pintype "bidirectional"))
      (node (ref "U3") (pin "4") (pinfunction "Y_4") (pintype "bidirectional"))
    )
    (net (code "37") (name "GND") (class "Default")
      (node (ref "ARDUINO_DUE1") (pin "GND") (pinfunction "GND_GND") (pintype "bidirectional"))
      (node (ref "ARDUINO_DUE1") (pin "GND_1") (pinfunction "GND_GND_1") (pintype "bidirectional"))
      (node (ref "ARDUINO_DUE1") (pin "GND_2") (pinfunction "GND_GND_2") (pintype "bidirectional"))
      (node (ref "ARDUINO_DUE1") (pin "GND_3") (pinfunction "GND_GND_3") (pintype "bidirectional"))
      (node (ref "ARDUINO_DUE1") (pin "GND_4") (pinfunction "GND_GND_4") (pintype "bidirectional"))
      (node (ref "C1") (pin "2") (pinfunction "2_2") (pintype "passive"))
      (node (ref "C10") (pin "1") (pinfunction "1_1") (pintype "passive"))
      (node (ref "C11") (pin "2") (pinfunction "2_2") (pintype "passive"))
      (node (ref "C12") (pin "2") (pinfunction "2_2") (pintype "passive"))
      (node (ref "C13") (pin "2") (pinfunction "2_2") (pintype "passive"))
      (node (ref "C2") (pin "1") (pinfunction "1_1") (pintype "passive"))
      (node (ref "C3") (pin "1") (pinfunction "1_1") (pintype "passive"))
      (node (ref "C4") (pin "1") (pinfunction "1_1") (pintype "passive"))
      (node (ref "C5") (pin "1") (pinfunction "1_1") (pintype "passive"))
      (node (ref "C6") (pin "2") (pinfunction "2_2") (pintype "passive"))
      (node (ref "C7") (pin "2") (pinfunction "2_2") (pintype "passive"))
      (node (ref "C8") (pin "2") (pinfunction "2_2") (pintype "passive"))
      (node (ref "C9") (pin "1") (pinfunction "1_1") (pintype "passive"))
      (node (ref "D1") (pin "A") (pinfunction "A_A") (pintype "passive"))
      (node (ref "D2") (pin "A") (pinfunction "A_A") (pintype "passive"))
      (node (ref "D3") (pin "A") (pinfunction "A_A") (pintype "passive"))
      (node (ref "D4") (pin "A") (pinfunction "A_A") (pintype "passive"))
      (node (ref "IC1") (pin "2") (pinfunction "C1_2") (pintype "bidirectional"))
      (node (ref "IC1") (pin "4") (pinfunction "C2_4") (pintype "bidirectional"))
      (node (ref "IC1") (pin "5") (pinfunction "ET1_5") (pintype "bidirectional"))
      (node (ref "IC1") (pin "7") (pinfunction "ET2_7") (pintype "bidirectional"))
      (node (ref "IC2") (pin "2") (pinfunction "C1_2") (pintype "bidirectional"))
      (node (ref "IC2") (pin "4") (pinfunction "C2_4") (pintype "bidirectional"))
      (node (ref "IC2") (pin "5") (pinfunction "ET1_5") (pintype "bidirectional"))
      (node (ref "IC2") (pin "7") (pinfunction "ET2_7") (pintype "bidirectional"))
      (node (ref "Q1") (pin "2") (pinfunction "E_2") (pintype "passive"))
      (node (ref "Q10") (pin "2") (pinfunction "E_2") (pintype "passive"))
      (node (ref "Q12") (pin "2") (pinfunction "S_2") (pintype "passive"))
      (node (ref "Q13") (pin "2") (pinfunction "E_2") (pintype "passive"))
      (node (ref "Q14") (pin "2") (pinfunction "E_2") (pintype "passive"))
      (node (ref "Q16") (pin "2") (pinfunction "S_2") (pintype "passive"))
      (node (ref "Q2") (pin "2") (pinfunction "E_2") (pintype "passive"))
      (node (ref "Q4") (pin "2") (pinfunction "S_2") (pintype "passive"))
      (node (ref "Q5") (pin "2") (pinfunction "E_2") (pintype "passive"))
      (node (ref "Q6") (pin "2") (pinfunction "E_2") (pintype "passive"))
      (node (ref "Q8") (pin "2") (pinfunction "S_2") (pintype "passive"))
      (node (ref "Q9") (pin "2") (pinfunction "E_2") (pintype "passive"))
      (node (ref "R13") (pin "1") (pinfunction "1_1") (pintype "passive"))
      (node (ref "R15") (pin "1") (pinfunction "1_1") (pintype "passive"))
      (node (ref "R23") (pin "1") (pinfunction "1_1") (pintype "passive"))
      (node (ref "R25") (pin "1") (pinfunction "1_1") (pintype "passive"))
      (node (ref "R33") (pin "1") (pinfunction "1_1") (pintype "passive"))
      (node (ref "R35") (pin "1") (pinfunction "1_1") (pintype "passive"))
      (node (ref "R43") (pin "1") (pinfunction "1_1") (pintype "passive"))
      (node (ref "R5") (pin "1") (pinfunction "1_1") (pintype "passive"))
      (node (ref "R62") (pin "1") (pinfunction "1_1") (pintype "passive"))
      (node (ref "R63") (pin "1") (pinfunction "1_1") (pintype "passive"))
      (node (ref "R64") (pin "1") (pinfunction "1_1") (pintype "passive"))
      (node (ref "R65") (pin "1") (pinfunction "1_1") (pintype "passive"))
      (node (ref "TVS") (pin "A") (pinfunction "A_A") (pintype "passive"))
      (node (ref "U$2") (pin "P$10") (pinfunction "P$10_P$10") (pintype "bidirectional"))
      (node (ref "U$2") (pin "P$12") (pinfunction "P$12_P$12") (pintype "bidirectional"))
      (node (ref "U$2") (pin "P$20") (pinfunction "P$20_P$20") (pintype "bidirectional"))
      (node (ref "U$2") (pin "P$5") (pinfunction "P$5_P$5") (pintype "bidirectional"))
      (node (ref "U1") (pin "PIN2") (pinfunction "GND_PIN2") (pintype "bidirectional"))
      (node (ref "U1") (pin "PIN8") (pinfunction "RS_PIN8") (pintype "bidirectional"))
      (node (ref "U2") (pin "3") (pinfunction "GND_3") (pintype "bidirectional"))
      (node (ref "U3") (pin "3") (pinfunction "GND_3") (pintype "bidirectional"))
      (node (ref "U9") (pin "P$2") (pinfunction "GND_P$2") (pintype "bidirectional"))
      (node (ref "ZEN") (pin "A") (pinfunction "A_A") (pintype "passive"))
    )
    (net (code "38") (name "Net-(ARDUINO_DUE1-Pad13)") (class "Default")
      (node (ref "ARDUINO_DUE1") (pin "13") (pinfunction "13_13") (pintype "bidirectional"))
      (node (ref "C8") (pin "1") (pinfunction "1_1") (pintype "passive"))
      (node (ref "R1") (pin "1") (pinfunction "1_1") (pintype "passive"))
      (node (ref "R2") (pin "2") (pinfunction "2_2") (pintype "passive"))
    )
    (net (code "39") (name "Net-(ARDUINO_DUE1-RX1_19)") (class "Default")
      (node (ref "ARDUINO_DUE1") (pin "19") (pinfunction "RX1_19_19") (pintype "bidirectional"))
      (node (ref "U2") (pin "4") (pinfunction "Y_4") (pintype "bidirectional"))
    )
    (net (code "40") (name "Net-(ARDUINO_DUE1-TX1_18)") (class "Default")
      (node (ref "ARDUINO_DUE1") (pin "18") (pinfunction "TX1_18_18") (pintype "bidirectional"))
      (node (ref "U3") (pin "1") (pinfunction "A_1") (pintype "bidirectional"))
      (node (ref "U3") (pin "2") (pinfunction "B_2") (pintype "bidirectional"))
    )
    (net (code "41") (name "Net-(C13-Pad1)") (class "Default")
      (node (ref "C13") (pin "1") (pinfunction "1_1") (pintype "passive"))
      (node (ref "R56") (pin "2") (pinfunction "2_2") (pintype "passive"))
      (node (ref "R57") (pin "2") (pinfunction "2_2") (pintype "passive"))
    )
    (net (code "42") (name "Net-(IC1-A1)") (class "Default")
      (node (ref "IC1") (pin "1") (pinfunction "A1_1") (pintype "bidirectional"))
      (node (ref "R44") (pin "1") (pinfunction "1_1") (pintype "passive"))
    )
    (net (code "43") (name "Net-(IC1-A2)") (class "Default")
      (node (ref "IC1") (pin "3") (pinfunction "A2_3") (pintype "bidirectional"))
      (node (ref "R45") (pin "1") (pinfunction "1_1") (pintype "passive"))
    )
    (net (code "44") (name "Net-(IC1-CT1)") (class "Default")
      (node (ref "IC1") (pin "6") (pinfunction "CT1_6") (pintype "bidirectional"))
      (node (ref "R46") (pin "2") (pinfunction "2_2") (pintype "passive"))
    )
    (net (code "45") (name "Net-(IC1-CT2)") (class "Default")
      (node (ref "IC1") (pin "8") (pinfunction "CT2_8") (pintype "bidirectional"))
      (node (ref "R47") (pin "2") (pinfunction "2_2") (pintype "passive"))
    )
    (net (code "46") (name "Net-(IC2-A1)") (class "Default")
      (node (ref "IC2") (pin "1") (pinfunction "A1_1") (pintype "bidirectional"))
      (node (ref "R50") (pin "1") (pinfunction "1_1") (pintype "passive"))
    )
    (net (code "47") (name "Net-(IC2-A2)") (class "Default")
      (node (ref "IC2") (pin "3") (pinfunction "A2_3") (pintype "bidirectional"))
      (node (ref "R51") (pin "1") (pinfunction "1_1") (pintype "passive"))
    )
    (net (code "48") (name "Net-(IC2-CT1)") (class "Default")
      (node (ref "IC2") (pin "6") (pinfunction "CT1_6") (pintype "bidirectional"))
      (node (ref "R52") (pin "2") (pinfunction "2_2") (pintype "passive"))
    )
    (net (code "49") (name "Net-(IC2-CT2)") (class "Default")
      (node (ref "IC2") (pin "8") (pinfunction "CT2_8") (pintype "bidirectional"))
      (node (ref "R53") (pin "2") (pinfunction "2_2") (pintype "passive"))
    )
    (net (code "50") (name "Net-(IC3A-I)") (class "Default")
      (node (ref "IC3") (pin "1") (pinfunction "I_1") (pintype "input"))
      (node (ref "R61") (pin "2") (pinfunction "2_2") (pintype "passive"))
      (node (ref "R62") (pin "2") (pinfunction "2_2") (pintype "passive"))
    )
    (net (code "51") (name "Net-(IC3B-I)") (class "Default")
      (node (ref "IC3") (pin "3") (pinfunction "I_3") (pintype "input"))
      (node (ref "R60") (pin "2") (pinfunction "2_2") (pintype "passive"))
      (node (ref "R63") (pin "2") (pinfunction "2_2") (pintype "passive"))
    )
    (net (code "52") (name "Net-(IC3C-I)") (class "Default")
      (node (ref "IC3") (pin "5") (pinfunction "I_5") (pintype "input"))
      (node (ref "R59") (pin "2") (pinfunction "2_2") (pintype "passive"))
      (node (ref "R64") (pin "2") (pinfunction "2_2") (pintype "passive"))
    )
    (net (code "53") (name "Net-(IC3D-I)") (class "Default")
      (node (ref "IC3") (pin "9") (pinfunction "I_9") (pintype "input"))
      (node (ref "R58") (pin "2") (pinfunction "2_2") (pintype "passive"))
      (node (ref "R65") (pin "2") (pinfunction "2_2") (pintype "passive"))
    )
    (net (code "54") (name "Net-(PTC-2)") (class "Default")
      (node (ref "D9") (pin "C") (pinfunction "C_C") (pintype "passive"))
      (node (ref "PTC") (pin "P$2") (pinfunction "2_P$2") (pintype "passive"))
      (node (ref "TVS") (pin "C") (pinfunction "C_C") (pintype "passive"))
    )
    (net (code "55") (name "Net-(Q1-B)") (class "Default")
      (node (ref "Q1") (pin "1") (pinfunction "B_1") (pintype "passive"))
      (node (ref "R3") (pin "2") (pinfunction "2_2") (pintype "passive"))
      (node (ref "R5") (pin "2") (pinfunction "2_2") (pintype "passive"))
    )
    (net (code "56") (name "Net-(Q1-C)") (class "Default")
      (node (ref "Q1") (pin "3") (pinfunction "C_3") (pintype "passive"))
      (node (ref "R6") (pin "1") (pinfunction "1_1") (pintype "passive"))
      (node (ref "R7") (pin "1") (pinfunction "1_1") (pintype "passive"))
    )
    (net (code "57") (name "Net-(Q2-B)") (class "Default")
      (node (ref "Q2") (pin "1") (pinfunction "B_1") (pintype "passive"))
      (node (ref "R11") (pin "1") (pinfunction "1_1") (pintype "passive"))
      (node (ref "R9") (pin "2") (pinfunction "2_2") (pintype "passive"))
    )
    (net (code "58") (name "Net-(Q2-C)") (class "Default")
      (node (ref "Q2") (pin "3") (pinfunction "C_3") (pintype "passive"))
      (node (ref "R10") (pin "1") (pinfunction "1_1") (pintype "passive"))
      (node (ref "R12") (pin "2") (pinfunction "2_2") (pintype "passive"))
    )
    (net (code "59") (name "Net-(Q3-G)") (class "Default")
      (node (ref "Q3") (pin "1") (pinfunction "G_1") (pintype "passive"))
      (node (ref "R7") (pin "2") (pinfunction "2_2") (pintype "passive"))
      (node (ref "R8") (pin "1") (pinfunction "1_1") (pintype "passive"))
    )
    (net (code "60") (name "Net-(Q4-G)") (class "Default")
      (node (ref "Q4") (pin "1") (pinfunction "G_1") (pintype "passive"))
      (node (ref "R12") (pin "1") (pinfunction "1_1") (pintype "passive"))
      (node (ref "R13") (pin "2") (pinfunction "2_2") (pintype "passive"))
    )
    (net (code "61") (name "Net-(Q5-B)") (class "Default")
      (node (ref "Q5") (pin "1") (pinfunction "B_1") (pintype "passive"))
      (node (ref "R14") (pin "2") (pinfunction "2_2") (pintype "passive"))
      (node (ref "R15") (pin "2") (pinfunction "2_2") (pintype "passive"))
    )
    (net (code "62") (name "Net-(Q5-C)") (class "Default")
      (node (ref "Q5") (pin "3") (pinfunction "C_3") (pintype "passive"))
      (node (ref "R16") (pin "1") (pinfunction "1_1") (pintype "passive"))
      (node (ref "R17") (pin "1") (pinfunction "1_1") (pintype "passive"))
    )
    (net (code "63") (name "Net-(Q6-B)") (class "Default")
      (node (ref "Q6") (pin "1") (pinfunction "B_1") (pintype "passive"))
      (node (ref "R19") (pin "2") (pinfunction "2_2") (pintype "passive"))
      (node (ref "R21") (pin "1") (pinfunction "1_1") (pintype "passive"))
    )
    (net (code "64") (name "Net-(Q6-C)") (class "Default")
      (node (ref "Q6") (pin "3") (pinfunction "C_3") (pintype "passive"))
      (node (ref "R20") (pin "1") (pinfunction "1_1") (pintype "passive"))
      (node (ref "R22") (pin "2") (pinfunction "2_2") (pintype "passive"))
    )
    (net (code "65") (name "Net-(Q7-G)") (class "Default")
      (node (ref "Q7") (pin "1") (pinfunction "G_1") (pintype "passive"))
      (node (ref "R17") (pin "2") (pinfunction "2_2") (pintype "passive"))
      (node (ref "R18") (pin "1") (pinfunction "1_1") (pintype "passive"))
    )
    (net (code "66") (name "Net-(Q8-G)") (class "Default")
      (node (ref "Q8") (pin "1") (pinfunction "G_1") (pintype "passive"))
      (node (ref "R22") (pin "1") (pinfunction "1_1") (pintype "passive"))
      (node (ref "R23") (pin "2") (pinfunction "2_2") (pintype "passive"))
    )
    (net (code "67") (name "Net-(Q9-B)") (class "Default")
      (node (ref "Q9") (pin "1") (pinfunction "B_1") (pintype "passive"))
      (node (ref "R24") (pin "2") (pinfunction "2_2") (pintype "passive"))
      (node (ref "R25") (pin "2") (pinfunction "2_2") (pintype "passive"))
    )
    (net (code "68") (name "Net-(Q9-C)") (class "Default")
      (node (ref "Q9") (pin "3") (pinfunction "C_3") (pintype "passive"))
      (node (ref "R26") (pin "1") (pinfunction "1_1") (pintype "passive"))
      (node (ref "R27") (pin "1") (pinfunction "1_1") (pintype "passive"))
    )
    (net (code "69") (name "Net-(Q10-B)") (class "Default")
      (node (ref "Q10") (pin "1") (pinfunction "B_1") (pintype "passive"))
      (node (ref "R29") (pin "2") (pinfunction "2_2") (pintype "passive"))
      (node (ref "R31") (pin "1") (pinfunction "1_1") (pintype "passive"))
    )
    (net (code "70") (name "Net-(Q10-C)") (class "Default")
      (node (ref "Q10") (pin "3") (pinfunction "C_3") (pintype "passive"))
      (node (ref "R30") (pin "1") (pinfunction "1_1") (pintype "passive"))
      (node (ref "R32") (pin "2") (pinfunction "2_2") (pintype "passive"))
    )
    (net (code "71") (name "Net-(Q11-G)") (class "Default")
      (node (ref "Q11") (pin "1") (pinfunction "G_1") (pintype "passive"))
      (node (ref "R27") (pin "2") (pinfunction "2_2") (pintype "passive"))
      (node (ref "R28") (pin "1") (pinfunction "1_1") (pintype "passive"))
    )
    (net (code "72") (name "Net-(Q12-G)") (class "Default")
      (node (ref "Q12") (pin "1") (pinfunction "G_1") (pintype "passive"))
      (node (ref "R32") (pin "1") (pinfunction "1_1") (pintype "passive"))
      (node (ref "R33") (pin "2") (pinfunction "2_2") (pintype "passive"))
    )
    (net (code "73") (name "Net-(Q13-B)") (class "Default")
      (node (ref "Q13") (pin "1") (pinfunction "B_1") (pintype "passive"))
      (node (ref "R34") (pin "2") (pinfunction "2_2") (pintype "passive"))
      (node (ref "R35") (pin "2") (pinfunction "2_2") (pintype "passive"))
    )
    (net (code "74") (name "Net-(Q13-C)") (class "Default")
      (node (ref "Q13") (pin "3") (pinfunction "C_3") (pintype "passive"))
      (node (ref "R36") (pin "1") (pinfunction "1_1") (pintype "passive"))
      (node (ref "R37") (pin "1") (pinfunction "1_1") (pintype "passive"))
    )
    (net (code "75") (name "Net-(Q14-B)") (class "Default")
      (node (ref "Q14") (pin "1") (pinfunction "B_1") (pintype "passive"))
      (node (ref "R39") (pin "2") (pinfunction "2_2") (pintype "passive"))
      (node (ref "R41") (pin "1") (pinfunction "1_1") (pintype "passive"))
    )
    (net (code "76") (name "Net-(Q14-C)") (class "Default")
      (node (ref "Q14") (pin "3") (pinfunction "C_3") (pintype "passive"))
      (node (ref "R40") (pin "1") (pinfunction "1_1") (pintype "passive"))
      (node (ref "R42") (pin "2") (pinfunction "2_2") (pintype "passive"))
    )
    (net (code "77") (name "Net-(Q15-G)") (class "Default")
      (node (ref "Q15") (pin "1") (pinfunction "G_1") (pintype "passive"))
      (node (ref "R37") (pin "2") (pinfunction "2_2") (pintype "passive"))
      (node (ref "R38") (pin "1") (pinfunction "1_1") (pintype "passive"))
    )
    (net (code "78") (name "Net-(Q16-G)") (class "Default")
      (node (ref "Q16") (pin "1") (pinfunction "G_1") (pintype "passive"))
      (node (ref "R42") (pin "1") (pinfunction "1_1") (pintype "passive"))
      (node (ref "R43") (pin "2") (pinfunction "2_2") (pintype "passive"))
    )
    (net (code "79") (name "Net-(U2-A)") (class "Default")
      (node (ref "C9") (pin "2") (pinfunction "2_2") (pintype "passive"))
      (node (ref "R4") (pin "2") (pinfunction "2_2") (pintype "passive"))
      (node (ref "U2") (pin "1") (pinfunction "A_1") (pintype "bidirectional"))
      (node (ref "U2") (pin "2") (pinfunction "B_2") (pintype "bidirectional"))
    )
    (net (code "80") (name "unconnected-(ARDUINO_DUE1-AN4-PadA4)") (class "Default")
      (node (ref "ARDUINO_DUE1") (pin "A4") (pinfunction "AN4_A4") (pintype "bidirectional"))
    )
    (net (code "81") (name "unconnected-(ARDUINO_DUE1-AN5-PadA5)") (class "Default")
      (node (ref "ARDUINO_DUE1") (pin "A5") (pinfunction "AN5_A5") (pintype "bidirectional"))
    )
    (net (code "82") (name "unconnected-(ARDUINO_DUE1-AN6-PadA6)") (class "Default")
      (node (ref "ARDUINO_DUE1") (pin "A6") (pinfunction "AN6_A6") (pintype "bidirectional"))
    )
    (net (code "83") (name "unconnected-(ARDUINO_DUE1-AN7-PadA7)") (class "Default")
      (node (ref "ARDUINO_DUE1") (pin "A7") (pinfunction "AN7_A7") (pintype "bidirectional"))
    )
    (net (code "84") (name "unconnected-(ARDUINO_DUE1-AN8-PadA8)") (class "Default")
      (node (ref "ARDUINO_DUE1") (pin "A8") (pinfunction "AN8_A8") (pintype "bidirectional"))
    )
    (net (code "85") (name "unconnected-(ARDUINO_DUE1-AN9-PadA9)") (class "Default")
      (node (ref "ARDUINO_DUE1") (pin "A9") (pinfunction "AN9_A9") (pintype "bidirectional"))
    )
    (net (code "86") (name "unconnected-(ARDUINO_DUE1-AN10-PadA10)") (class "Default")
      (node (ref "ARDUINO_DUE1") (pin "A10") (pinfunction "AN10_A10") (pintype "bidirectional"))
    )
    (net (code "87") (name "unconnected-(ARDUINO_DUE1-AN11-PadA11)") (class "Default")
      (node (ref "ARDUINO_DUE1") (pin "A11") (pinfunction "AN11_A11") (pintype "bidirectional"))
    )
    (net (code "88") (name "unconnected-(ARDUINO_DUE1-NC-PadNC_2)") (class "Default")
      (node (ref "ARDUINO_DUE1") (pin "NC_2") (pinfunction "NC_NC_2") (pintype "no_connect"))
    )
    (net (code "89") (name "unconnected-(ARDUINO_DUE1-Pad10)") (class "Default")
      (node (ref "ARDUINO_DUE1") (pin "10") (pinfunction "10_10") (pintype "bidirectional"))
    )
    (net (code "90") (name "unconnected-(ARDUINO_DUE1-Pad11)") (class "Default")
      (node (ref "ARDUINO_DUE1") (pin "11") (pinfunction "11_11") (pintype "bidirectional"))
    )
    (net (code "91") (name "unconnected-(ARDUINO_DUE1-Pad12)") (class "Default")
      (node (ref "ARDUINO_DUE1") (pin "12") (pinfunction "12_12") (pintype "bidirectional"))
    )
    (net (code "92") (name "unconnected-(ARDUINO_DUE1-Pad22)") (class "Default")
      (node (ref "ARDUINO_DUE1") (pin "22") (pinfunction "22_22") (pintype "bidirectional"))
    )
    (net (code "93") (name "unconnected-(ARDUINO_DUE1-Pad23)") (class "Default")
      (node (ref "ARDUINO_DUE1") (pin "23") (pinfunction "23_23") (pintype "bidirectional"))
    )
    (net (code "94") (name "unconnected-(ARDUINO_DUE1-Pad24)") (class "Default")
      (node (ref "ARDUINO_DUE1") (pin "24") (pinfunction "24_24") (pintype "bidirectional"))
    )
    (net (code "95") (name "unconnected-(ARDUINO_DUE1-Pad25)") (class "Default")
      (node (ref "ARDUINO_DUE1") (pin "25") (pinfunction "25_25") (pintype "bidirectional"))
    )
    (net (code "96") (name "unconnected-(ARDUINO_DUE1-Pad26)") (class "Default")
      (node (ref "ARDUINO_DUE1") (pin "26") (pinfunction "26_26") (pintype "bidirectional"))
    )
    (net (code "97") (name "unconnected-(ARDUINO_DUE1-Pad27)") (class "Default")
      (node (ref "ARDUINO_DUE1") (pin "27") (pinfunction "27_27") (pintype "bidirectional"))
    )
    (net (code "98") (name "unconnected-(ARDUINO_DUE1-Pad28)") (class "Default")
      (node (ref "ARDUINO_DUE1") (pin "28") (pinfunction "28_28") (pintype "bidirectional"))
    )
    (net (code "99") (name "unconnected-(ARDUINO_DUE1-Pad29)") (class "Default")
      (node (ref "ARDUINO_DUE1") (pin "29") (pinfunction "29_29") (pintype "bidirectional"))
    )
    (net (code "100") (name "unconnected-(ARDUINO_DUE1-Pad30)") (class "Default")
      (node (ref "ARDUINO_DUE1") (pin "30") (pinfunction "30_30") (pintype "bidirectional"))
    )
    (net (code "101") (name "unconnected-(ARDUINO_DUE1-Pad31)") (class "Default")
      (node (ref "ARDUINO_DUE1") (pin "31") (pinfunction "31_31") (pintype "bidirectional"))
    )
    (net (code "102") (name "unconnected-(ARDUINO_DUE1-Pad32)") (class "Default")
      (node (ref "ARDUINO_DUE1") (pin "32") (pinfunction "32_32") (pintype "bidirectional"))
    )
    (net (code "103") (name "unconnected-(ARDUINO_DUE1-Pad33)") (class "Default")
      (node (ref "ARDUINO_DUE1") (pin "33") (pinfunction "33_33") (pintype "bidirectional"))
    )
    (net (code "104") (name "unconnected-(ARDUINO_DUE1-Pad34)") (class "Default")
      (node (ref "ARDUINO_DUE1") (pin "34") (pinfunction "34_34") (pintype "bidirectional"))
    )
    (net (code "105") (name "unconnected-(ARDUINO_DUE1-Pad35)") (class "Default")
      (node (ref "ARDUINO_DUE1") (pin "35") (pinfunction "35_35") (pintype "bidirectional"))
    )
    (net (code "106") (name "unconnected-(ARDUINO_DUE1-Pad36)") (class "Default")
      (node (ref "ARDUINO_DUE1") (pin "36") (pinfunction "36_36") (pintype "bidirectional"))
    )
    (net (code "107") (name "unconnected-(ARDUINO_DUE1-Pad37)") (class "Default")
      (node (ref "ARDUINO_DUE1") (pin "37") (pinfunction "37_37") (pintype "bidirectional"))
    )
    (net (code "108") (name "unconnected-(ARDUINO_DUE1-Pad38)") (class "Default")
      (node (ref "ARDUINO_DUE1") (pin "38") (pinfunction "38_38") (pintype "bidirectional"))
    )
    (net (code "109") (name "unconnected-(ARDUINO_DUE1-Pad39)") (class "Default")
      (node (ref "ARDUINO_DUE1") (pin "39") (pinfunction "39_39") (pintype "bidirectional"))
    )
    (net (code "110") (name "unconnected-(ARDUINO_DUE1-Pad40)") (class "Default")
      (node (ref "ARDUINO_DUE1") (pin "40") (pinfunction "40_40") (pintype "bidirectional"))
    )
    (net (code "111") (name "unconnected-(ARDUINO_DUE1-Pad41)") (class "Default")
      (node (ref "ARDUINO_DUE1") (pin "41") (pinfunction "41_41") (pintype "bidirectional"))
    )
    (net (code "112") (name "unconnected-(ARDUINO_DUE1-Pad42)") (class "Default")
      (node (ref "ARDUINO_DUE1") (pin "42") (pinfunction "42_42") (pintype "bidirectional"))
    )
    (net (code "113") (name "unconnected-(ARDUINO_DUE1-Pad43)") (class "Default")
      (node (ref "ARDUINO_DUE1") (pin "43") (pinfunction "43_43") (pintype "bidirectional"))
    )
    (net (code "114") (name "unconnected-(ARDUINO_DUE1-Pad44)") (class "Default")
      (node (ref "ARDUINO_DUE1") (pin "44") (pinfunction "44_44") (pintype "bidirectional"))
    )
    (net (code "115") (name "unconnected-(ARDUINO_DUE1-Pad45)") (class "Default")
      (node (ref "ARDUINO_DUE1") (pin "45") (pinfunction "45_45") (pintype "bidirectional"))
    )
    (net (code "116") (name "unconnected-(ARDUINO_DUE1-Pad46)") (class "Default")
      (node (ref "ARDUINO_DUE1") (pin "46") (pinfunction "46_46") (pintype "bidirectional"))
    )
    (net (code "117") (name "unconnected-(ARDUINO_DUE1-Pad47)") (class "Default")
      (node (ref "ARDUINO_DUE1") (pin "47") (pinfunction "47_47") (pintype "bidirectional"))
    )
    (net (code "118") (name "unconnected-(ARDUINO_DUE1-Pad48)") (class "Default")
      (node (ref "ARDUINO_DUE1") (pin "48") (pinfunction "48_48") (pintype "bidirectional"))
    )
    (net (code "119") (name "unconnected-(ARDUINO_DUE1-Pad49)") (class "Default")
      (node (ref "ARDUINO_DUE1") (pin "49") (pinfunction "49_49") (pintype "bidirectional"))
    )
    (net (code "120") (name "unconnected-(ARDUINO_DUE1-Pad50)") (class "Default")
      (node (ref "ARDUINO_DUE1") (pin "50") (pinfunction "50_50") (pintype "bidirectional"))
    )
    (net (code "121") (name "unconnected-(ARDUINO_DUE1-Pad52)") (class "Default")
      (node (ref "ARDUINO_DUE1") (pin "52") (pinfunction "52_52") (pintype "bidirectional"))
    )
    (net (code "122") (name "unconnected-(ARDUINO_DUE1-PadAREF)") (class "Default")
      (node (ref "ARDUINO_DUE1") (pin "AREF") (pinfunction "AREF_AREF") (pintype "bidirectional"))
    )
    (net (code "123") (name "unconnected-(ARDUINO_DUE1-PadCANRX)") (class "Default")
      (node (ref "ARDUINO_DUE1") (pin "CANRX") (pinfunction "CANRX_CANRX") (pintype "bidirectional"))
    )
    (net (code "124") (name "unconnected-(ARDUINO_DUE1-PadCANTX)") (class "Default")
      (node (ref "ARDUINO_DUE1") (pin "CANTX") (pinfunction "CANTX_CANTX") (pintype "bidirectional"))
    )
    (net (code "125") (name "unconnected-(ARDUINO_DUE1-PadDAC1)") (class "Default")
      (node (ref "ARDUINO_DUE1") (pin "DAC1") (pinfunction "DAC1_DAC1") (pintype "bidirectional"))
    )
    (net (code "126") (name "unconnected-(ARDUINO_DUE1-PadIOREF)") (class "Default")
      (node (ref "ARDUINO_DUE1") (pin "IOREF") (pinfunction "IOREF_IOREF") (pintype "bidirectional"))
    )
    (net (code "127") (name "unconnected-(ARDUINO_DUE1-PadRESET)") (class "Default")
      (node (ref "ARDUINO_DUE1") (pin "RESET") (pinfunction "RESET_RESET") (pintype "bidirectional"))
    )
    (net (code "128") (name "unconnected-(ARDUINO_DUE1-PadSCL1)") (class "Default")
      (node (ref "ARDUINO_DUE1") (pin "SCL1") (pinfunction "SCL1_SCL1") (pintype "bidirectional"))
    )
    (net (code "129") (name "unconnected-(ARDUINO_DUE1-PadSDA1)") (class "Default")
      (node (ref "ARDUINO_DUE1") (pin "SDA1") (pinfunction "SDA1_SDA1") (pintype "bidirectional"))
    )
    (net (code "130") (name "unconnected-(ARDUINO_DUE1-PadVIN)") (class "Default")
      (node (ref "ARDUINO_DUE1") (pin "VIN") (pinfunction "VIN_VIN") (pintype "bidirectional"))
    )
    (net (code "131") (name "unconnected-(ARDUINO_DUE1-RX0<0-Pad0)") (class "Default")
      (node (ref "ARDUINO_DUE1") (pin "0") (pinfunction "RX0<0_0") (pintype "bidirectional"))
    )
    (net (code "132") (name "unconnected-(ARDUINO_DUE1-RX2_17-Pad17)") (class "Default")
      (node (ref "ARDUINO_DUE1") (pin "17") (pinfunction "RX2_17_17") (pintype "bidirectional"))
    )
    (net (code "133") (name "unconnected-(ARDUINO_DUE1-RX3_15-Pad15)") (class "Default")
      (node (ref "ARDUINO_DUE1") (pin "15") (pinfunction "RX3_15_15") (pintype "bidirectional"))
    )
    (net (code "134") (name "unconnected-(ARDUINO_DUE1-SCL_21-Pad21)") (class "Default")
      (node (ref "ARDUINO_DUE1") (pin "21") (pinfunction "SCL_21_21") (pintype "bidirectional"))
    )
    (net (code "135") (name "unconnected-(ARDUINO_DUE1-SDA_20-Pad20)") (class "Default")
      (node (ref "ARDUINO_DUE1") (pin "20") (pinfunction "SDA_20_20") (pintype "bidirectional"))
    )
    (net (code "136") (name "unconnected-(ARDUINO_DUE1-TX0>1-Pad1)") (class "Default")
      (node (ref "ARDUINO_DUE1") (pin "1") (pinfunction "TX0>1_1") (pintype "bidirectional"))
    )
    (net (code "137") (name "unconnected-(ARDUINO_DUE1-TX2_16-Pad16)") (class "Default")
      (node (ref "ARDUINO_DUE1") (pin "16") (pinfunction "TX2_16_16") (pintype "bidirectional"))
    )
    (net (code "138") (name "unconnected-(ARDUINO_DUE1-TX3_14-Pad14)") (class "Default")
      (node (ref "ARDUINO_DUE1") (pin "14") (pinfunction "TX3_14_14") (pintype "bidirectional"))
    )
    (net (code "139") (name "unconnected-(IC3E-O-Pad10)") (class "Default")
      (node (ref "IC3") (pin "10") (pinfunction "O_10") (pintype "output"))
    )
    (net (code "140") (name "unconnected-(IC3F-O-Pad12)") (class "Default")
      (node (ref "IC3") (pin "12") (pinfunction "O_12") (pintype "output"))
    )
  )
)
